# turntable.net
KiCad netlist of a schematic drawn in EAGLE
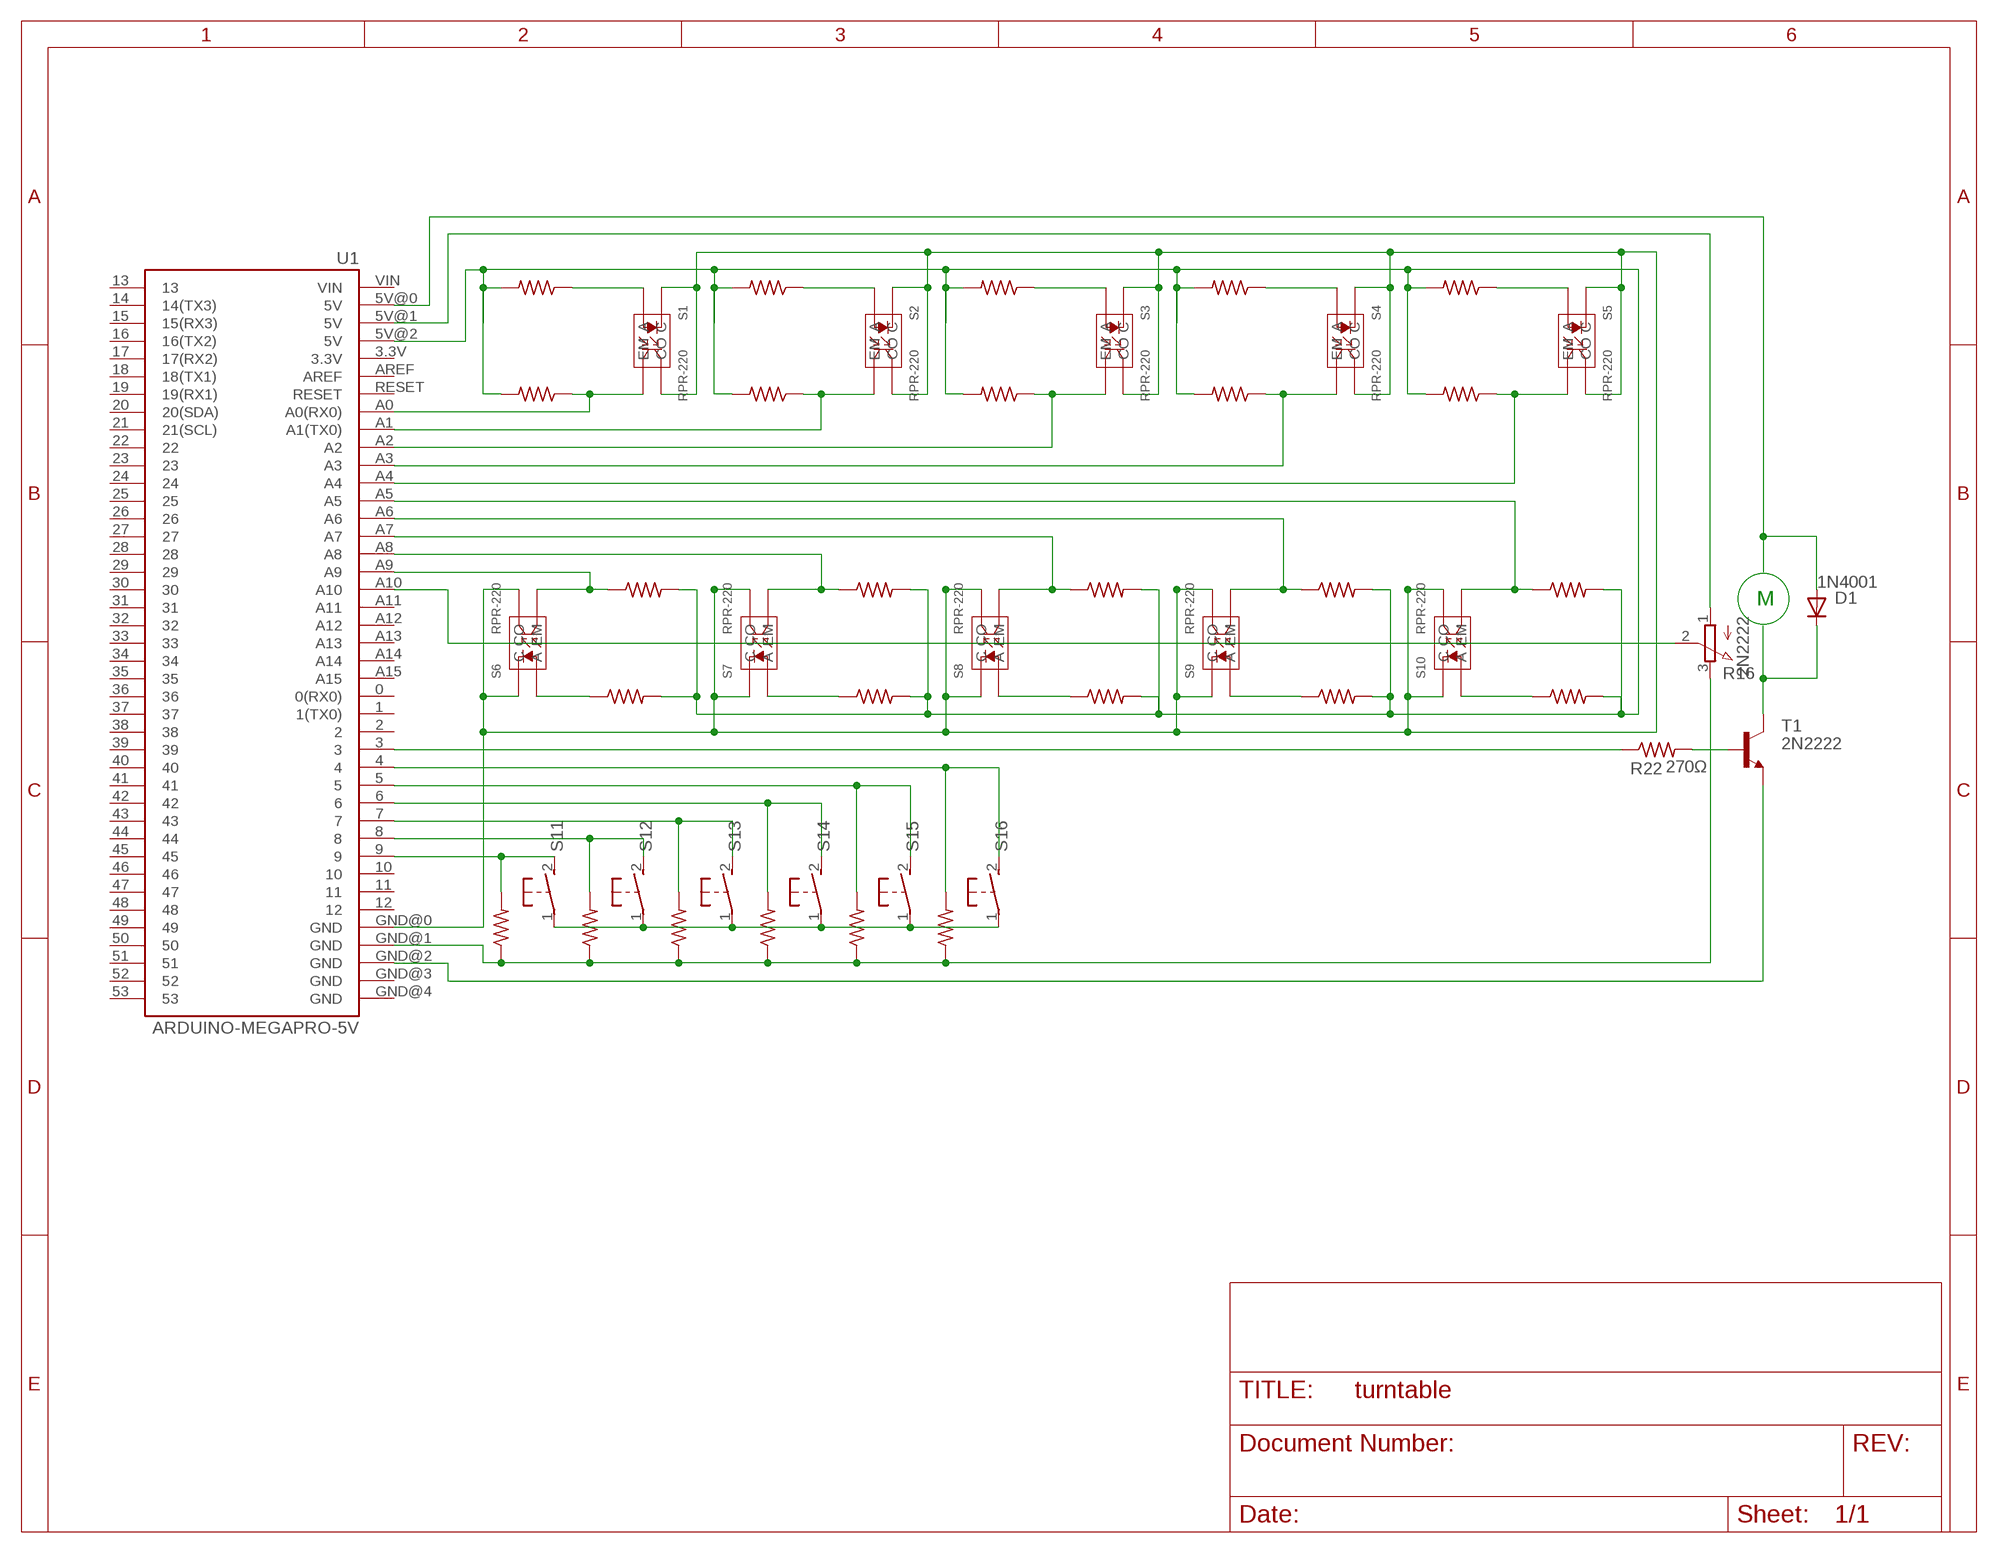
[diagram p0: schematic, sheet 1]

(export (version "E")
  (design (tool "Eeschema 10.0.6"))
  (components
    (comp (ref "D1")
      (value "1N4001")
      (footprint "eagle-import:DO41-10")
      (libsource (lib "eagle-import") (part "1N4004"))
    )
    (comp (ref "R1")
      (value "270Ω")
      (footprint "eagle-import:0204V")
      (libsource (lib "eagle-import") (part "R-US_0204/2V"))
    )
    (comp (ref "R2")
      (value "270Ω")
      (footprint "eagle-import:0204V")
      (libsource (lib "eagle-import") (part "R-US_0204/2V"))
    )
    (comp (ref "R3")
      (value "270Ω")
      (footprint "eagle-import:0204V")
      (libsource (lib "eagle-import") (part "R-US_0204/2V"))
    )
    (comp (ref "R4")
      (value "270Ω")
      (footprint "eagle-import:0204V")
      (libsource (lib "eagle-import") (part "R-US_0204/2V"))
    )
    (comp (ref "R5")
      (value "270Ω")
      (footprint "eagle-import:0204V")
      (libsource (lib "eagle-import") (part "R-US_0204/2V"))
    )
    (comp (ref "R6")
      (value "270Ω")
      (footprint "eagle-import:0204V")
      (libsource (lib "eagle-import") (part "R-US_0204/2V"))
    )
    (comp (ref "R7")
      (value "270Ω")
      (footprint "eagle-import:0204V")
      (libsource (lib "eagle-import") (part "R-US_0204/2V"))
    )
    (comp (ref "R8")
      (value "270Ω")
      (footprint "eagle-import:0204V")
      (libsource (lib "eagle-import") (part "R-US_0204/2V"))
    )
    (comp (ref "R9")
      (value "270Ω")
      (footprint "eagle-import:0204V")
      (libsource (lib "eagle-import") (part "R-US_0204/2V"))
    )
    (comp (ref "R10")
      (value "270Ω")
      (footprint "eagle-import:0204V")
      (libsource (lib "eagle-import") (part "R-US_0204/2V"))
    )
    (comp (ref "R11")
      (value "270Ω")
      (footprint "eagle-import:0204V")
      (libsource (lib "eagle-import") (part "R-US_0204/2V"))
    )
    (comp (ref "R12")
      (value "270Ω")
      (footprint "eagle-import:0204V")
      (libsource (lib "eagle-import") (part "R-US_0204/2V"))
    )
    (comp (ref "R13")
      (value "270Ω")
      (footprint "eagle-import:0204V")
      (libsource (lib "eagle-import") (part "R-US_0204/2V"))
    )
    (comp (ref "R14")
      (value "270Ω")
      (footprint "eagle-import:0204V")
      (libsource (lib "eagle-import") (part "R-US_0204/2V"))
    )
    (comp (ref "R15")
      (value "270Ω")
      (footprint "eagle-import:0204V")
      (libsource (lib "eagle-import") (part "R-US_0204/2V"))
    )
    (comp (ref "R16")
      (value "2N2222")
      (footprint "eagle-import:3RP_1610N")
      (libsource (lib "eagle-import") (part "3RP/1610N"))
    )
    (comp (ref "R17")
      (value "270Ω")
      (footprint "eagle-import:0204V")
      (libsource (lib "eagle-import") (part "R-US_0204/2V"))
    )
    (comp (ref "R18")
      (value "270Ω")
      (footprint "eagle-import:0204V")
      (libsource (lib "eagle-import") (part "R-US_0204/2V"))
    )
    (comp (ref "R19")
      (value "270Ω")
      (footprint "eagle-import:0204V")
      (libsource (lib "eagle-import") (part "R-US_0204/2V"))
    )
    (comp (ref "R20")
      (value "270Ω")
      (footprint "eagle-import:0204V")
      (libsource (lib "eagle-import") (part "R-US_0204/2V"))
    )
    (comp (ref "R21")
      (value "270Ω")
      (footprint "eagle-import:0204V")
      (libsource (lib "eagle-import") (part "R-US_0204/2V"))
    )
    (comp (ref "R22")
      (value "270Ω")
      (footprint "eagle-import:0204V")
      (libsource (lib "eagle-import") (part "R-US_0204/2V"))
    )
    (comp (ref "R23")
      (value "270Ω")
      (footprint "eagle-import:0204V")
      (libsource (lib "eagle-import") (part "R-US_0204/2V"))
    )
    (comp (ref "R24")
      (value "270Ω")
      (footprint "eagle-import:0204V")
      (libsource (lib "eagle-import") (part "R-US_0204/2V"))
    )
    (comp (ref "R25")
      (value "270Ω")
      (footprint "eagle-import:0204V")
      (libsource (lib "eagle-import") (part "R-US_0204/2V"))
    )
    (comp (ref "R26")
      (value "270Ω")
      (footprint "eagle-import:0204V")
      (libsource (lib "eagle-import") (part "R-US_0204/2V"))
    )
    (comp (ref "R27")
      (value "270Ω")
      (footprint "eagle-import:0204V")
      (libsource (lib "eagle-import") (part "R-US_0204/2V"))
    )
    (comp (ref "R28")
      (value "270Ω")
      (footprint "eagle-import:0204V")
      (libsource (lib "eagle-import") (part "R-US_0204/2V"))
    )
    (comp (ref "S1")
      (value "RPR-220")
      (footprint "eagle-import:SNR4-8.7X4.5X5.8MM")
      (fields (field (name "MF") "Rohm"))
      (libsource (lib "eagle-import") (part "OPTICAL-RPR-220(4P-6.4X4.9MM)"))
    )
    (comp (ref "S2")
      (value "RPR-220")
      (footprint "eagle-import:SNR4-8.7X4.5X5.8MM")
      (fields (field (name "MF") "Rohm"))
      (libsource (lib "eagle-import") (part "OPTICAL-RPR-220(4P-6.4X4.9MM)"))
    )
    (comp (ref "S3")
      (value "RPR-220")
      (footprint "eagle-import:SNR4-8.7X4.5X5.8MM")
      (fields (field (name "MF") "Rohm"))
      (libsource (lib "eagle-import") (part "OPTICAL-RPR-220(4P-6.4X4.9MM)"))
    )
    (comp (ref "S4")
      (value "RPR-220")
      (footprint "eagle-import:SNR4-8.7X4.5X5.8MM")
      (fields (field (name "MF") "Rohm"))
      (libsource (lib "eagle-import") (part "OPTICAL-RPR-220(4P-6.4X4.9MM)"))
    )
    (comp (ref "S5")
      (value "RPR-220")
      (footprint "eagle-import:SNR4-8.7X4.5X5.8MM")
      (fields (field (name "MF") "Rohm"))
      (libsource (lib "eagle-import") (part "OPTICAL-RPR-220(4P-6.4X4.9MM)"))
    )
    (comp (ref "S6")
      (value "RPR-220")
      (footprint "eagle-import:SNR4-8.7X4.5X5.8MM")
      (fields (field (name "MF") "Rohm"))
      (libsource (lib "eagle-import") (part "OPTICAL-RPR-220(4P-6.4X4.9MM)"))
    )
    (comp (ref "S7")
      (value "RPR-220")
      (footprint "eagle-import:SNR4-8.7X4.5X5.8MM")
      (fields (field (name "MF") "Rohm"))
      (libsource (lib "eagle-import") (part "OPTICAL-RPR-220(4P-6.4X4.9MM)"))
    )
    (comp (ref "S8")
      (value "RPR-220")
      (footprint "eagle-import:SNR4-8.7X4.5X5.8MM")
      (fields (field (name "MF") "Rohm"))
      (libsource (lib "eagle-import") (part "OPTICAL-RPR-220(4P-6.4X4.9MM)"))
    )
    (comp (ref "S9")
      (value "RPR-220")
      (footprint "eagle-import:SNR4-8.7X4.5X5.8MM")
      (fields (field (name "MF") "Rohm"))
      (libsource (lib "eagle-import") (part "OPTICAL-RPR-220(4P-6.4X4.9MM)"))
    )
    (comp (ref "S10")
      (value "RPR-220")
      (footprint "eagle-import:SNR4-8.7X4.5X5.8MM")
      (fields (field (name "MF") "Rohm"))
      (libsource (lib "eagle-import") (part "OPTICAL-RPR-220(4P-6.4X4.9MM)"))
    )
    (comp (ref "S11")
      (value "31-XX")
      (footprint "eagle-import:B3F-31XX")
      (libsource (lib "eagle-import") (part "31-XX"))
    )
    (comp (ref "S12")
      (value "31-XX")
      (footprint "eagle-import:B3F-31XX")
      (libsource (lib "eagle-import") (part "31-XX"))
    )
    (comp (ref "S13")
      (value "31-XX")
      (footprint "eagle-import:B3F-31XX")
      (libsource (lib "eagle-import") (part "31-XX"))
    )
    (comp (ref "S14")
      (value "31-XX")
      (footprint "eagle-import:B3F-31XX")
      (libsource (lib "eagle-import") (part "31-XX"))
    )
    (comp (ref "S15")
      (value "31-XX")
      (footprint "eagle-import:B3F-31XX")
      (libsource (lib "eagle-import") (part "31-XX"))
    )
    (comp (ref "S16")
      (value "31-XX")
      (footprint "eagle-import:B3F-31XX")
      (libsource (lib "eagle-import") (part "31-XX"))
    )
    (comp (ref "T1")
      (value "2N2222")
      (footprint "eagle-import:TO92-EBC-OVAL")
      (libsource (lib "eagle-import") (part "2N2222"))
    )
    (comp (ref "U1")
      (value "ARDUINO-MEGAPRO-5V")
      (footprint "eagle-import:ARDUINO_MEGA-PRO-5V")
      (libsource (lib "eagle-import") (part "ARDUINO-MEGAPRO-5V"))
    )
  )
  (nets
    (net (code "1") (name "Net-(D1-PadA)") (class "Default")
      (node (ref "D1") (pin "A") (pinfunction "A_A") (pintype "passive"))
      (node (ref "U1") (pin "5V@0") (pinfunction "5V_5V@0") (pintype "bidirectional"))
    )
    (net (code "2") (name "Net-(D1-PadC)") (class "Default")
      (node (ref "D1") (pin "C") (pinfunction "C_C") (pintype "passive"))
      (node (ref "T1") (pin "C") (pinfunction "C_C") (pintype "passive"))
    )
    (net (code "3") (name "Net-(R1-Pad2)") (class "Default")
      (node (ref "R1") (pin "2") (pinfunction "2_2") (pintype "passive"))
      (node (ref "R10") (pin "2") (pinfunction "2_2") (pintype "passive"))
      (node (ref "R11") (pin "2") (pinfunction "2_2") (pintype "passive"))
      (node (ref "R12") (pin "2") (pinfunction "2_2") (pintype "passive"))
      (node (ref "R13") (pin "2") (pinfunction "2_2") (pintype "passive"))
      (node (ref "R14") (pin "2") (pinfunction "2_2") (pintype "passive"))
      (node (ref "R15") (pin "2") (pinfunction "2_2") (pintype "passive"))
      (node (ref "R17") (pin "2") (pinfunction "2_2") (pintype "passive"))
      (node (ref "R18") (pin "2") (pinfunction "2_2") (pintype "passive"))
      (node (ref "R19") (pin "2") (pinfunction "2_2") (pintype "passive"))
      (node (ref "R2") (pin "2") (pinfunction "2_2") (pintype "passive"))
      (node (ref "R20") (pin "2") (pinfunction "2_2") (pintype "passive"))
      (node (ref "R21") (pin "2") (pinfunction "2_2") (pintype "passive"))
      (node (ref "R3") (pin "2") (pinfunction "2_2") (pintype "passive"))
      (node (ref "R4") (pin "2") (pinfunction "2_2") (pintype "passive"))
      (node (ref "R5") (pin "2") (pinfunction "2_2") (pintype "passive"))
      (node (ref "R6") (pin "2") (pinfunction "2_2") (pintype "passive"))
      (node (ref "R7") (pin "2") (pinfunction "2_2") (pintype "passive"))
      (node (ref "R8") (pin "2") (pinfunction "2_2") (pintype "passive"))
      (node (ref "R9") (pin "2") (pinfunction "2_2") (pintype "passive"))
      (node (ref "U1") (pin "5V@2") (pinfunction "5V_5V@2") (pintype "bidirectional"))
    )
    (net (code "4") (name "Net-(R16-A)") (class "Default")
      (node (ref "R16") (pin "1") (pinfunction "A_1") (pintype "passive"))
      (node (ref "U1") (pin "5V@1") (pinfunction "5V_5V@1") (pintype "bidirectional"))
    )
    (net (code "5") (name "Net-(R16-E)") (class "Default")
      (node (ref "R16") (pin "3") (pinfunction "E_3") (pintype "passive"))
      (node (ref "R23") (pin "1") (pinfunction "1_1") (pintype "passive"))
      (node (ref "R24") (pin "1") (pinfunction "1_1") (pintype "passive"))
      (node (ref "R25") (pin "1") (pinfunction "1_1") (pintype "passive"))
      (node (ref "R26") (pin "1") (pinfunction "1_1") (pintype "passive"))
      (node (ref "R27") (pin "1") (pinfunction "1_1") (pintype "passive"))
      (node (ref "R28") (pin "1") (pinfunction "1_1") (pintype "passive"))
      (node (ref "U1") (pin "GND@1") (pinfunction "GND_GND@1") (pintype "bidirectional"))
    )
    (net (code "6") (name "Net-(R16-S)") (class "Default")
      (node (ref "R16") (pin "2") (pinfunction "S_2") (pintype "passive"))
      (node (ref "U1") (pin "A10") (pinfunction "A10_A10") (pintype "bidirectional"))
    )
    (net (code "7") (name "Net-(R22-Pad1)") (class "Default")
      (node (ref "R22") (pin "1") (pinfunction "1_1") (pintype "passive"))
      (node (ref "U1") (pin "3") (pinfunction "3_3") (pintype "bidirectional"))
    )
    (net (code "8") (name "Net-(R22-Pad2)") (class "Default")
      (node (ref "R22") (pin "2") (pinfunction "2_2") (pintype "passive"))
      (node (ref "T1") (pin "B") (pinfunction "B_B") (pintype "passive"))
    )
    (net (code "9") (name "Net-(S1-A)") (class "Default")
      (node (ref "R1") (pin "1") (pinfunction "1_1") (pintype "passive"))
      (node (ref "S1") (pin "1") (pinfunction "A_1") (pintype "bidirectional"))
    )
    (net (code "10") (name "Net-(S1-C)") (class "Default")
      (node (ref "S1") (pin "2") (pinfunction "C_2") (pintype "bidirectional"))
      (node (ref "S1") (pin "4") (pinfunction "CO_4") (pintype "bidirectional"))
      (node (ref "S10") (pin "2") (pinfunction "C_2") (pintype "bidirectional"))
      (node (ref "S10") (pin "4") (pinfunction "CO_4") (pintype "bidirectional"))
      (node (ref "S2") (pin "2") (pinfunction "C_2") (pintype "bidirectional"))
      (node (ref "S2") (pin "4") (pinfunction "CO_4") (pintype "bidirectional"))
      (node (ref "S3") (pin "2") (pinfunction "C_2") (pintype "bidirectional"))
      (node (ref "S3") (pin "4") (pinfunction "CO_4") (pintype "bidirectional"))
      (node (ref "S4") (pin "2") (pinfunction "C_2") (pintype "bidirectional"))
      (node (ref "S4") (pin "4") (pinfunction "CO_4") (pintype "bidirectional"))
      (node (ref "S5") (pin "2") (pinfunction "C_2") (pintype "bidirectional"))
      (node (ref "S5") (pin "4") (pinfunction "CO_4") (pintype "bidirectional"))
      (node (ref "S6") (pin "2") (pinfunction "C_2") (pintype "bidirectional"))
      (node (ref "S6") (pin "4") (pinfunction "CO_4") (pintype "bidirectional"))
      (node (ref "S7") (pin "2") (pinfunction "C_2") (pintype "bidirectional"))
      (node (ref "S7") (pin "4") (pinfunction "CO_4") (pintype "bidirectional"))
      (node (ref "S8") (pin "2") (pinfunction "C_2") (pintype "bidirectional"))
      (node (ref "S8") (pin "4") (pinfunction "CO_4") (pintype "bidirectional"))
      (node (ref "S9") (pin "2") (pinfunction "C_2") (pintype "bidirectional"))
      (node (ref "S9") (pin "4") (pinfunction "CO_4") (pintype "bidirectional"))
      (node (ref "U1") (pin "GND@0") (pinfunction "GND_GND@0") (pintype "bidirectional"))
    )
    (net (code "11") (name "Net-(S1-EM)") (class "Default")
      (node (ref "R6") (pin "1") (pinfunction "1_1") (pintype "passive"))
      (node (ref "S1") (pin "3") (pinfunction "EM_3") (pintype "bidirectional"))
      (node (ref "U1") (pin "A0") (pinfunction "A0(RX0)_A0") (pintype "bidirectional"))
    )
    (net (code "12") (name "Net-(S2-A)") (class "Default")
      (node (ref "R2") (pin "1") (pinfunction "1_1") (pintype "passive"))
      (node (ref "S2") (pin "1") (pinfunction "A_1") (pintype "bidirectional"))
    )
    (net (code "13") (name "Net-(S2-EM)") (class "Default")
      (node (ref "R7") (pin "1") (pinfunction "1_1") (pintype "passive"))
      (node (ref "S2") (pin "3") (pinfunction "EM_3") (pintype "bidirectional"))
      (node (ref "U1") (pin "A1") (pinfunction "A1(TX0)_A1") (pintype "bidirectional"))
    )
    (net (code "14") (name "Net-(S3-A)") (class "Default")
      (node (ref "R3") (pin "1") (pinfunction "1_1") (pintype "passive"))
      (node (ref "S3") (pin "1") (pinfunction "A_1") (pintype "bidirectional"))
    )
    (net (code "15") (name "Net-(S3-EM)") (class "Default")
      (node (ref "R8") (pin "1") (pinfunction "1_1") (pintype "passive"))
      (node (ref "S3") (pin "3") (pinfunction "EM_3") (pintype "bidirectional"))
      (node (ref "U1") (pin "A2") (pinfunction "A2_A2") (pintype "bidirectional"))
    )
    (net (code "16") (name "Net-(S4-A)") (class "Default")
      (node (ref "R4") (pin "1") (pinfunction "1_1") (pintype "passive"))
      (node (ref "S4") (pin "1") (pinfunction "A_1") (pintype "bidirectional"))
    )
    (net (code "17") (name "Net-(S4-EM)") (class "Default")
      (node (ref "R9") (pin "1") (pinfunction "1_1") (pintype "passive"))
      (node (ref "S4") (pin "3") (pinfunction "EM_3") (pintype "bidirectional"))
      (node (ref "U1") (pin "A3") (pinfunction "A3_A3") (pintype "bidirectional"))
    )
    (net (code "18") (name "Net-(S5-A)") (class "Default")
      (node (ref "R5") (pin "1") (pinfunction "1_1") (pintype "passive"))
      (node (ref "S5") (pin "1") (pinfunction "A_1") (pintype "bidirectional"))
    )
    (net (code "19") (name "Net-(S5-EM)") (class "Default")
      (node (ref "R10") (pin "1") (pinfunction "1_1") (pintype "passive"))
      (node (ref "S5") (pin "3") (pinfunction "EM_3") (pintype "bidirectional"))
      (node (ref "U1") (pin "A4") (pinfunction "A4_A4") (pintype "bidirectional"))
    )
    (net (code "20") (name "Net-(S6-A)") (class "Default")
      (node (ref "R17") (pin "1") (pinfunction "1_1") (pintype "passive"))
      (node (ref "S6") (pin "1") (pinfunction "A_1") (pintype "bidirectional"))
    )
    (net (code "21") (name "Net-(S6-EM)") (class "Default")
      (node (ref "R11") (pin "1") (pinfunction "1_1") (pintype "passive"))
      (node (ref "S6") (pin "3") (pinfunction "EM_3") (pintype "bidirectional"))
      (node (ref "U1") (pin "A9") (pinfunction "A9_A9") (pintype "bidirectional"))
    )
    (net (code "22") (name "Net-(S7-A)") (class "Default")
      (node (ref "R18") (pin "1") (pinfunction "1_1") (pintype "passive"))
      (node (ref "S7") (pin "1") (pinfunction "A_1") (pintype "bidirectional"))
    )
    (net (code "23") (name "Net-(S7-EM)") (class "Default")
      (node (ref "R12") (pin "1") (pinfunction "1_1") (pintype "passive"))
      (node (ref "S7") (pin "3") (pinfunction "EM_3") (pintype "bidirectional"))
      (node (ref "U1") (pin "A8") (pinfunction "A8_A8") (pintype "bidirectional"))
    )
    (net (code "24") (name "Net-(S8-A)") (class "Default")
      (node (ref "R19") (pin "1") (pinfunction "1_1") (pintype "passive"))
      (node (ref "S8") (pin "1") (pinfunction "A_1") (pintype "bidirectional"))
    )
    (net (code "25") (name "Net-(S8-EM)") (class "Default")
      (node (ref "R13") (pin "1") (pinfunction "1_1") (pintype "passive"))
      (node (ref "S8") (pin "3") (pinfunction "EM_3") (pintype "bidirectional"))
      (node (ref "U1") (pin "A7") (pinfunction "A7_A7") (pintype "bidirectional"))
    )
    (net (code "26") (name "Net-(S9-A)") (class "Default")
      (node (ref "R20") (pin "1") (pinfunction "1_1") (pintype "passive"))
      (node (ref "S9") (pin "1") (pinfunction "A_1") (pintype "bidirectional"))
    )
    (net (code "27") (name "Net-(S9-EM)") (class "Default")
      (node (ref "R14") (pin "1") (pinfunction "1_1") (pintype "passive"))
      (node (ref "S9") (pin "3") (pinfunction "EM_3") (pintype "bidirectional"))
      (node (ref "U1") (pin "A6") (pinfunction "A6_A6") (pintype "bidirectional"))
    )
    (net (code "28") (name "Net-(S10-A)") (class "Default")
      (node (ref "R21") (pin "1") (pinfunction "1_1") (pintype "passive"))
      (node (ref "S10") (pin "1") (pinfunction "A_1") (pintype "bidirectional"))
    )
    (net (code "29") (name "Net-(S10-EM)") (class "Default")
      (node (ref "R15") (pin "1") (pinfunction "1_1") (pintype "passive"))
      (node (ref "S10") (pin "3") (pinfunction "EM_3") (pintype "bidirectional"))
      (node (ref "U1") (pin "A5") (pinfunction "A5_A5") (pintype "bidirectional"))
    )
    (net (code "30") (name "Net-(S11-P)") (class "Default")
      (node (ref "S11") (pin "1") (pinfunction "P_1") (pintype "passive"))
      (node (ref "S12") (pin "1") (pinfunction "P_1") (pintype "passive"))
      (node (ref "S13") (pin "1") (pinfunction "P_1") (pintype "passive"))
      (node (ref "S14") (pin "1") (pinfunction "P_1") (pintype "passive"))
      (node (ref "S15") (pin "1") (pinfunction "P_1") (pintype "passive"))
      (node (ref "S16") (pin "1") (pinfunction "P_1") (pintype "passive"))
    )
    (net (code "31") (name "Net-(S11-S)") (class "Default")
      (node (ref "R23") (pin "2") (pinfunction "2_2") (pintype "passive"))
      (node (ref "S11") (pin "2") (pinfunction "S_2") (pintype "passive"))
      (node (ref "U1") (pin "9") (pinfunction "9_9") (pintype "bidirectional"))
    )
    (net (code "32") (name "Net-(S12-S)") (class "Default")
      (node (ref "R24") (pin "2") (pinfunction "2_2") (pintype "passive"))
      (node (ref "S12") (pin "2") (pinfunction "S_2") (pintype "passive"))
      (node (ref "U1") (pin "8") (pinfunction "8_8") (pintype "bidirectional"))
    )
    (net (code "33") (name "Net-(S13-S)") (class "Default")
      (node (ref "R25") (pin "2") (pinfunction "2_2") (pintype "passive"))
      (node (ref "S13") (pin "2") (pinfunction "S_2") (pintype "passive"))
      (node (ref "U1") (pin "7") (pinfunction "7_7") (pintype "bidirectional"))
    )
    (net (code "34") (name "Net-(S14-S)") (class "Default")
      (node (ref "R26") (pin "2") (pinfunction "2_2") (pintype "passive"))
      (node (ref "S14") (pin "2") (pinfunction "S_2") (pintype "passive"))
      (node (ref "U1") (pin "6") (pinfunction "6_6") (pintype "bidirectional"))
    )
    (net (code "35") (name "Net-(S15-S)") (class "Default")
      (node (ref "R27") (pin "2") (pinfunction "2_2") (pintype "passive"))
      (node (ref "S15") (pin "2") (pinfunction "S_2") (pintype "passive"))
      (node (ref "U1") (pin "5") (pinfunction "5_5") (pintype "bidirectional"))
    )
    (net (code "36") (name "Net-(S16-S)") (class "Default")
      (node (ref "R28") (pin "2") (pinfunction "2_2") (pintype "passive"))
      (node (ref "S16") (pin "2") (pinfunction "S_2") (pintype "passive"))
      (node (ref "U1") (pin "4") (pinfunction "4_4") (pintype "bidirectional"))
    )
    (net (code "37") (name "Net-(T1-PadE)") (class "Default")
      (node (ref "T1") (pin "E") (pinfunction "E_E") (pintype "passive"))
      (node (ref "U1") (pin "GND@2") (pinfunction "GND_GND@2") (pintype "bidirectional"))
    )
    (net (code "38") (name "unconnected-(U1-0(RX0)-Pad0)") (class "Default")
      (node (ref "U1") (pin "0") (pinfunction "0(RX0)_0") (pintype "bidirectional"))
    )
    (net (code "39") (name "unconnected-(U1-1(TX0)-Pad1)") (class "Default")
      (node (ref "U1") (pin "1") (pinfunction "1(TX0)_1") (pintype "bidirectional"))
    )
    (net (code "40") (name "unconnected-(U1-14(TX3)-Pad14)") (class "Default")
      (node (ref "U1") (pin "14") (pinfunction "14(TX3)_14") (pintype "bidirectional"))
    )
    (net (code "41") (name "unconnected-(U1-15(RX3)-Pad15)") (class "Default")
      (node (ref "U1") (pin "15") (pinfunction "15(RX3)_15") (pintype "bidirectional"))
    )
    (net (code "42") (name "unconnected-(U1-16(TX2)-Pad16)") (class "Default")
      (node (ref "U1") (pin "16") (pinfunction "16(TX2)_16") (pintype "bidirectional"))
    )
    (net (code "43") (name "unconnected-(U1-17(RX2)-Pad17)") (class "Default")
      (node (ref "U1") (pin "17") (pinfunction "17(RX2)_17") (pintype "bidirectional"))
    )
    (net (code "44") (name "unconnected-(U1-18(TX1)-Pad18)") (class "Default")
      (node (ref "U1") (pin "18") (pinfunction "18(TX1)_18") (pintype "bidirectional"))
    )
    (net (code "45") (name "unconnected-(U1-19(RX1)-Pad19)") (class "Default")
      (node (ref "U1") (pin "19") (pinfunction "19(RX1)_19") (pintype "bidirectional"))
    )
    (net (code "46") (name "unconnected-(U1-20(SDA)-Pad20)") (class "Default")
      (node (ref "U1") (pin "20") (pinfunction "20(SDA)_20") (pintype "bidirectional"))
    )
    (net (code "47") (name "unconnected-(U1-21(SCL)-Pad21)") (class "Default")
      (node (ref "U1") (pin "21") (pinfunction "21(SCL)_21") (pintype "bidirectional"))
    )
    (net (code "48") (name "unconnected-(U1-GND-PadGND@3)") (class "Default")
      (node (ref "U1") (pin "GND@3") (pinfunction "GND_GND@3") (pintype "bidirectional"))
    )
    (net (code "49") (name "unconnected-(U1-GND-PadGND@4)") (class "Default")
      (node (ref "U1") (pin "GND@4") (pinfunction "GND_GND@4") (pintype "bidirectional"))
    )
    (net (code "50") (name "unconnected-(U1-Pad2)") (class "Default")
      (node (ref "U1") (pin "2") (pinfunction "2_2") (pintype "bidirectional"))
    )
    (net (code "51") (name "unconnected-(U1-Pad3.3V)") (class "Default")
      (node (ref "U1") (pin "3.3V") (pinfunction "3.3V_3.3V") (pintype "bidirectional"))
    )
    (net (code "52") (name "unconnected-(U1-Pad10)") (class "Default")
      (node (ref "U1") (pin "10") (pinfunction "10_10") (pintype "bidirectional"))
    )
    (net (code "53") (name "unconnected-(U1-Pad11)") (class "Default")
      (node (ref "U1") (pin "11") (pinfunction "11_11") (pintype "bidirectional"))
    )
    (net (code "54") (name "unconnected-(U1-Pad12)") (class "Default")
      (node (ref "U1") (pin "12") (pinfunction "12_12") (pintype "bidirectional"))
    )
    (net (code "55") (name "unconnected-(U1-Pad13)") (class "Default")
      (node (ref "U1") (pin "13") (pinfunction "13_13") (pintype "bidirectional"))
    )
    (net (code "56") (name "unconnected-(U1-Pad22)") (class "Default")
      (node (ref "U1") (pin "22") (pinfunction "22_22") (pintype "bidirectional"))
    )
    (net (code "57") (name "unconnected-(U1-Pad23)") (class "Default")
      (node (ref "U1") (pin "23") (pinfunction "23_23") (pintype "bidirectional"))
    )
    (net (code "58") (name "unconnected-(U1-Pad24)") (class "Default")
      (node (ref "U1") (pin "24") (pinfunction "24_24") (pintype "bidirectional"))
    )
    (net (code "59") (name "unconnected-(U1-Pad25)") (class "Default")
      (node (ref "U1") (pin "25") (pinfunction "25_25") (pintype "bidirectional"))
    )
    (net (code "60") (name "unconnected-(U1-Pad26)") (class "Default")
      (node (ref "U1") (pin "26") (pinfunction "26_26") (pintype "bidirectional"))
    )
    (net (code "61") (name "unconnected-(U1-Pad27)") (class "Default")
      (node (ref "U1") (pin "27") (pinfunction "27_27") (pintype "bidirectional"))
    )
    (net (code "62") (name "unconnected-(U1-Pad28)") (class "Default")
      (node (ref "U1") (pin "28") (pinfunction "28_28") (pintype "bidirectional"))
    )
    (net (code "63") (name "unconnected-(U1-Pad29)") (class "Default")
      (node (ref "U1") (pin "29") (pinfunction "29_29") (pintype "bidirectional"))
    )
    (net (code "64") (name "unconnected-(U1-Pad30)") (class "Default")
      (node (ref "U1") (pin "30") (pinfunction "30_30") (pintype "bidirectional"))
    )
    (net (code "65") (name "unconnected-(U1-Pad31)") (class "Default")
      (node (ref "U1") (pin "31") (pinfunction "31_31") (pintype "bidirectional"))
    )
    (net (code "66") (name "unconnected-(U1-Pad32)") (class "Default")
      (node (ref "U1") (pin "32") (pinfunction "32_32") (pintype "bidirectional"))
    )
    (net (code "67") (name "unconnected-(U1-Pad33)") (class "Default")
      (node (ref "U1") (pin "33") (pinfunction "33_33") (pintype "bidirectional"))
    )
    (net (code "68") (name "unconnected-(U1-Pad34)") (class "Default")
      (node (ref "U1") (pin "34") (pinfunction "34_34") (pintype "bidirectional"))
    )
    (net (code "69") (name "unconnected-(U1-Pad35)") (class "Default")
      (node (ref "U1") (pin "35") (pinfunction "35_35") (pintype "bidirectional"))
    )
    (net (code "70") (name "unconnected-(U1-Pad36)") (class "Default")
      (node (ref "U1") (pin "36") (pinfunction "36_36") (pintype "bidirectional"))
    )
    (net (code "71") (name "unconnected-(U1-Pad37)") (class "Default")
      (node (ref "U1") (pin "37") (pinfunction "37_37") (pintype "bidirectional"))
    )
    (net (code "72") (name "unconnected-(U1-Pad38)") (class "Default")
      (node (ref "U1") (pin "38") (pinfunction "38_38") (pintype "bidirectional"))
    )
    (net (code "73") (name "unconnected-(U1-Pad39)") (class "Default")
      (node (ref "U1") (pin "39") (pinfunction "39_39") (pintype "bidirectional"))
    )
    (net (code "74") (name "unconnected-(U1-Pad40)") (class "Default")
      (node (ref "U1") (pin "40") (pinfunction "40_40") (pintype "bidirectional"))
    )
    (net (code "75") (name "unconnected-(U1-Pad41)") (class "Default")
      (node (ref "U1") (pin "41") (pinfunction "41_41") (pintype "bidirectional"))
    )
    (net (code "76") (name "unconnected-(U1-Pad42)") (class "Default")
      (node (ref "U1") (pin "42") (pinfunction "42_42") (pintype "bidirectional"))
    )
    (net (code "77") (name "unconnected-(U1-Pad43)") (class "Default")
      (node (ref "U1") (pin "43") (pinfunction "43_43") (pintype "bidirectional"))
    )
    (net (code "78") (name "unconnected-(U1-Pad44)") (class "Default")
      (node (ref "U1") (pin "44") (pinfunction "44_44") (pintype "bidirectional"))
    )
    (net (code "79") (name "unconnected-(U1-Pad45)") (class "Default")
      (node (ref "U1") (pin "45") (pinfunction "45_45") (pintype "bidirectional"))
    )
    (net (code "80") (name "unconnected-(U1-Pad46)") (class "Default")
      (node (ref "U1") (pin "46") (pinfunction "46_46") (pintype "bidirectional"))
    )
    (net (code "81") (name "unconnected-(U1-Pad47)") (class "Default")
      (node (ref "U1") (pin "47") (pinfunction "47_47") (pintype "bidirectional"))
    )
    (net (code "82") (name "unconnected-(U1-Pad48)") (class "Default")
      (node (ref "U1") (pin "48") (pinfunction "48_48") (pintype "bidirectional"))
    )
    (net (code "83") (name "unconnected-(U1-Pad49)") (class "Default")
      (node (ref "U1") (pin "49") (pinfunction "49_49") (pintype "bidirectional"))
    )
    (net (code "84") (name "unconnected-(U1-Pad50)") (class "Default")
      (node (ref "U1") (pin "50") (pinfunction "50_50") (pintype "bidirectional"))
    )
    (net (code "85") (name "unconnected-(U1-Pad51)") (class "Default")
      (node (ref "U1") (pin "51") (pinfunction "51_51") (pintype "bidirectional"))
    )
    (net (code "86") (name "unconnected-(U1-Pad52)") (class "Default")
      (node (ref "U1") (pin "52") (pinfunction "52_52") (pintype "bidirectional"))
    )
    (net (code "87") (name "unconnected-(U1-Pad53)") (class "Default")
      (node (ref "U1") (pin "53") (pinfunction "53_53") (pintype "bidirectional"))
    )
    (net (code "88") (name "unconnected-(U1-PadA11)") (class "Default")
      (node (ref "U1") (pin "A11") (pinfunction "A11_A11") (pintype "bidirectional"))
    )
    (net (code "89") (name "unconnected-(U1-PadA12)") (class "Default")
      (node (ref "U1") (pin "A12") (pinfunction "A12_A12") (pintype "bidirectional"))
    )
    (net (code "90") (name "unconnected-(U1-PadA13)") (class "Default")
      (node (ref "U1") (pin "A13") (pinfunction "A13_A13") (pintype "bidirectional"))
    )
    (net (code "91") (name "unconnected-(U1-PadA14)") (class "Default")
      (node (ref "U1") (pin "A14") (pinfunction "A14_A14") (pintype "bidirectional"))
    )
    (net (code "92") (name "unconnected-(U1-PadA15)") (class "Default")
      (node (ref "U1") (pin "A15") (pinfunction "A15_A15") (pintype "bidirectional"))
    )
    (net (code "93") (name "unconnected-(U1-PadAREF)") (class "Default")
      (node (ref "U1") (pin "AREF") (pinfunction "AREF_AREF") (pintype "bidirectional"))
    )
    (net (code "94") (name "unconnected-(U1-PadRESET)") (class "Default")
      (node (ref "U1") (pin "RESET") (pinfunction "RESET_RESET") (pintype "bidirectional"))
    )
    (net (code "95") (name "unconnected-(U1-PadVIN)") (class "Default")
      (node (ref "U1") (pin "VIN") (pinfunction "VIN_VIN") (pintype "bidirectional"))
    )
  )
)
